# ProtoShieldMega.net
KiCad netlist of a schematic drawn in EAGLE
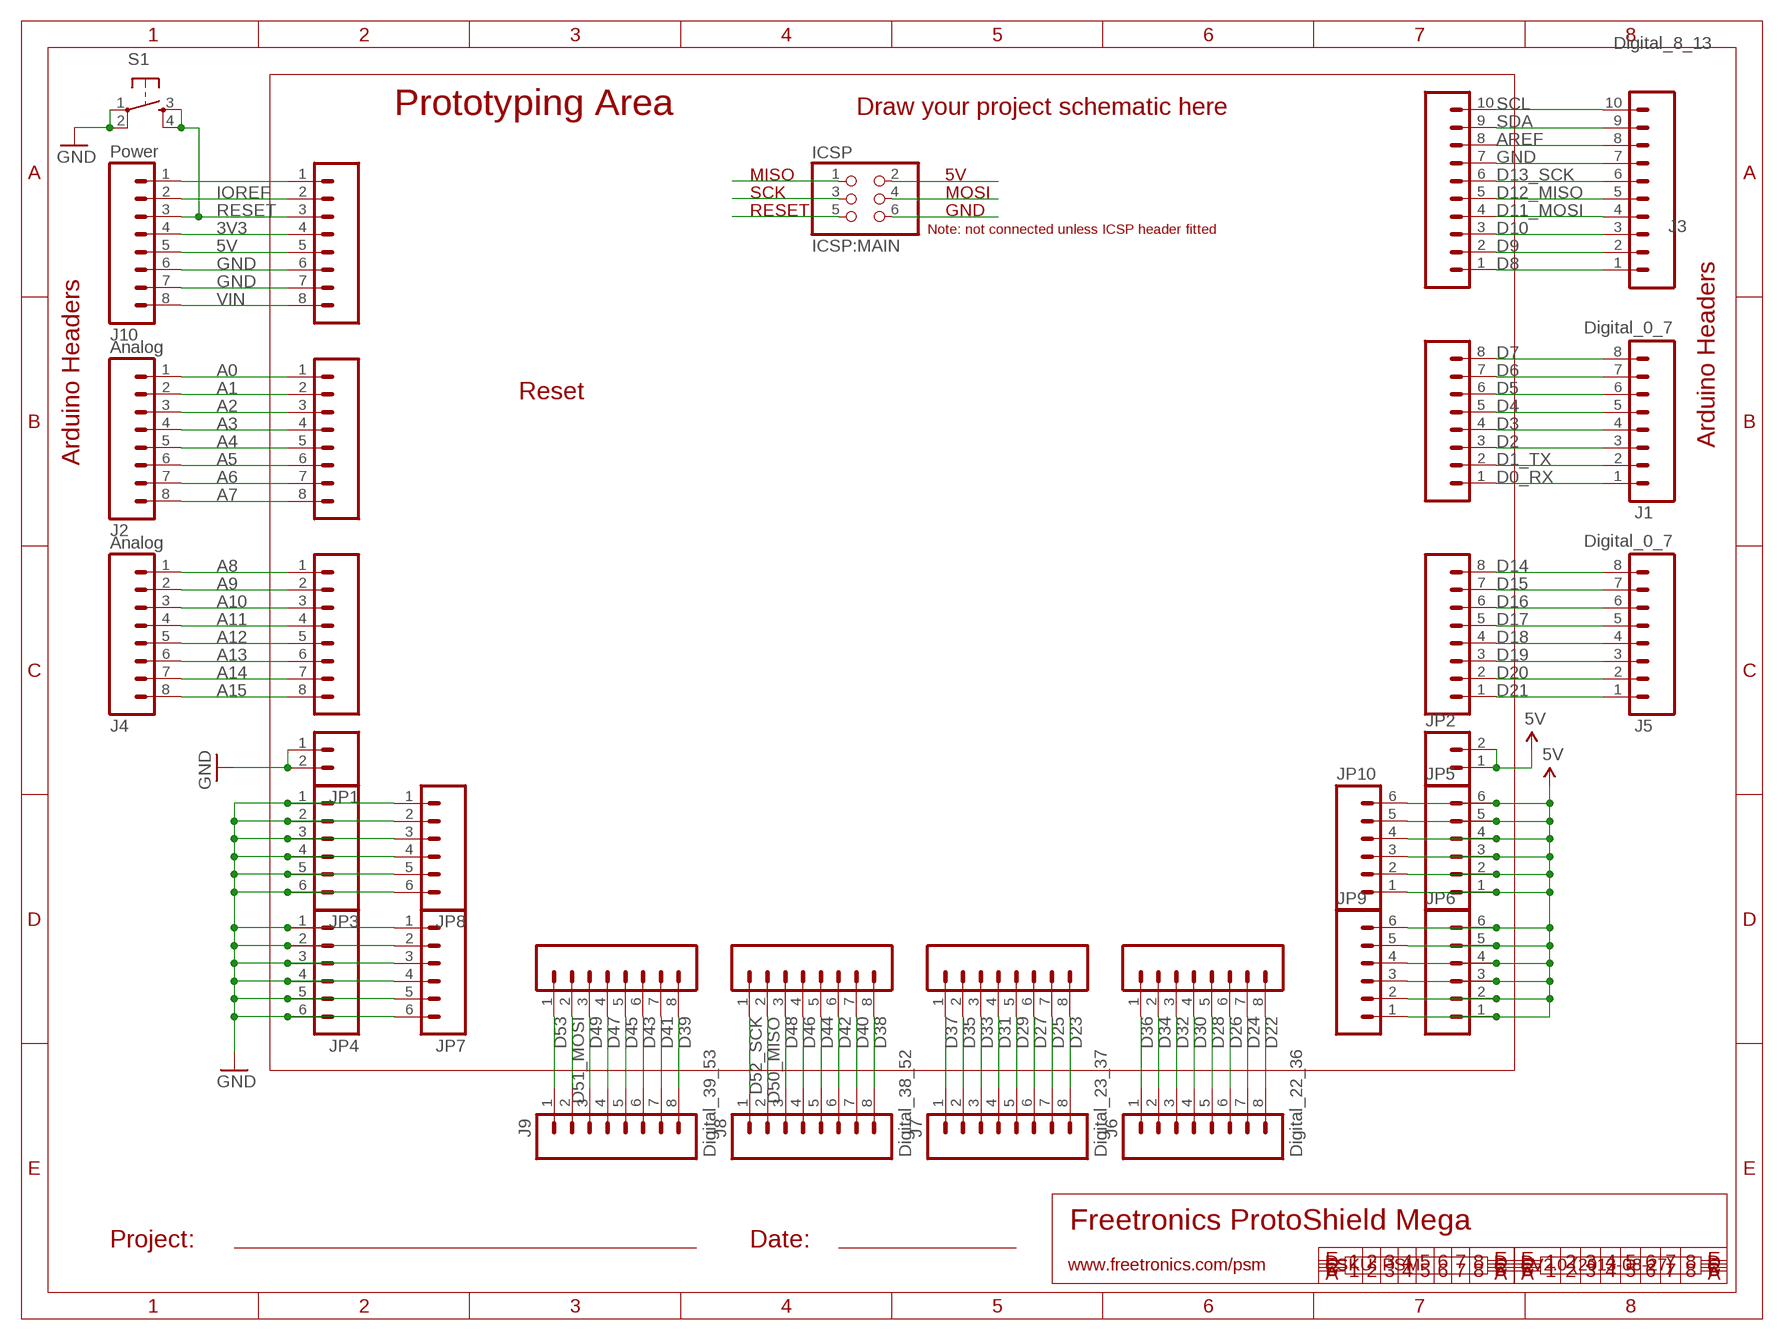
[diagram p0: schematic, sheet 1]

(export (version "E")
  (design (tool "Eeschema 10.0.6"))
  (components
    (comp (ref "ICSP")
      (value "ICSP:MAIN")
      (footprint "eagle-import:2X03")
      (libsource (lib "eagle-import") (part "PINHD-2X3"))
    )
    (comp (ref "J1")
      (value "Digital_0_7")
      (footprint "eagle-import:1X08")
      (libsource (lib "eagle-import") (part "M08"))
    )
    (comp (ref "J2")
      (value "Analog")
      (footprint "eagle-import:1X08")
      (libsource (lib "eagle-import") (part "freetronics-master-v1_M08"))
    )
    (comp (ref "J3")
      (value "Digital_8_13")
      (footprint "eagle-import:1X10")
      (libsource (lib "eagle-import") (part "M100.1"))
    )
    (comp (ref "J4")
      (value "Analog")
      (footprint "eagle-import:1X08")
      (libsource (lib "eagle-import") (part "freetronics-master-v1_M08"))
    )
    (comp (ref "J5")
      (value "Digital_0_7")
      (footprint "eagle-import:1X08")
      (libsource (lib "eagle-import") (part "M08"))
    )
    (comp (ref "J6")
      (value "Digital_22_36")
      (footprint "eagle-import:1X08")
      (libsource (lib "eagle-import") (part "M08"))
    )
    (comp (ref "J7")
      (value "Digital_23_37")
      (footprint "eagle-import:1X08")
      (libsource (lib "eagle-import") (part "M08"))
    )
    (comp (ref "J8")
      (value "Digital_38_52")
      (footprint "eagle-import:1X08")
      (libsource (lib "eagle-import") (part "M08"))
    )
    (comp (ref "J9")
      (value "Digital_39_53")
      (footprint "eagle-import:1X08")
      (libsource (lib "eagle-import") (part "M08"))
    )
    (comp (ref "J10")
      (value "Power")
      (footprint "eagle-import:1X08")
      (libsource (lib "eagle-import") (part "freetronics-master-v1_M08"))
    )
    (comp (ref "JP1")
      (value "M02PTH")
      (footprint "eagle-import:1X02")
      (libsource (lib "eagle-import") (part "M02PTH"))
    )
    (comp (ref "JP2")
      (value "M02PTH")
      (footprint "eagle-import:1X02")
      (libsource (lib "eagle-import") (part "M02PTH"))
    )
    (comp (ref "JP3")
      (value "M06SIP")
      (footprint "eagle-import:1X06")
      (libsource (lib "eagle-import") (part "M06SIP"))
    )
    (comp (ref "JP4")
      (value "M06SIP")
      (footprint "eagle-import:1X06")
      (libsource (lib "eagle-import") (part "M06SIP"))
    )
    (comp (ref "JP5")
      (value "M06SIP")
      (footprint "eagle-import:1X06")
      (libsource (lib "eagle-import") (part "M06SIP"))
    )
    (comp (ref "JP6")
      (value "M06SIP")
      (footprint "eagle-import:1X06")
      (libsource (lib "eagle-import") (part "M06SIP"))
    )
    (comp (ref "JP7")
      (value "M06SIP")
      (footprint "eagle-import:1X06")
      (libsource (lib "eagle-import") (part "M06SIP"))
    )
    (comp (ref "JP8")
      (value "M06SIP")
      (footprint "eagle-import:1X06")
      (libsource (lib "eagle-import") (part "M06SIP"))
    )
    (comp (ref "JP9")
      (value "M06SIP")
      (footprint "eagle-import:1X06")
      (libsource (lib "eagle-import") (part "M06SIP"))
    )
    (comp (ref "JP10")
      (value "M06SIP")
      (footprint "eagle-import:1X06")
      (libsource (lib "eagle-import") (part "M06SIP"))
    )
    (comp (ref "S1")
      (value "TAC_SWITCHPTH")
      (footprint "eagle-import:TACTILE-PTH")
      (libsource (lib "eagle-import") (part "TAC_SWITCHPTH"))
    )
    (comp (ref "SL1")
      (value "Digital_0_7")
      (footprint "eagle-import:1X08")
      (libsource (lib "eagle-import") (part "M08"))
    )
    (comp (ref "SL2")
      (value "Analog")
      (footprint "eagle-import:1X08")
      (libsource (lib "eagle-import") (part "freetronics-master-v1_M08"))
    )
    (comp (ref "SL3")
      (value "Digital_8_13")
      (footprint "eagle-import:1X10")
      (libsource (lib "eagle-import") (part "M100.1"))
    )
    (comp (ref "SL4")
      (value "Analog")
      (footprint "eagle-import:1X08")
      (libsource (lib "eagle-import") (part "freetronics-master-v1_M08"))
    )
    (comp (ref "SL5")
      (value "Digital_0_7")
      (footprint "eagle-import:1X08")
      (libsource (lib "eagle-import") (part "M08"))
    )
    (comp (ref "SL6")
      (value "Digital_0_7")
      (footprint "eagle-import:1X08")
      (libsource (lib "eagle-import") (part "M08"))
    )
    (comp (ref "SL7")
      (value "Digital_0_7")
      (footprint "eagle-import:1X08")
      (libsource (lib "eagle-import") (part "M08"))
    )
    (comp (ref "SL8")
      (value "Digital_0_7")
      (footprint "eagle-import:1X08")
      (libsource (lib "eagle-import") (part "M08"))
    )
    (comp (ref "SL9")
      (value "Digital_0_7")
      (footprint "eagle-import:1X08")
      (libsource (lib "eagle-import") (part "M08"))
    )
    (comp (ref "SLP")
      (value "Power")
      (footprint "eagle-import:1X08")
      (libsource (lib "eagle-import") (part "freetronics-master-v1_M08"))
    )
  )
  (nets
    (net (code "1") (name "/3V3") (class "Default")
      (node (ref "J10") (pin "4") (pinfunction "4_4") (pintype "passive"))
      (node (ref "SLP") (pin "4") (pinfunction "4_4") (pintype "passive"))
    )
    (net (code "2") (name "/A0") (class "Default")
      (node (ref "J2") (pin "1") (pinfunction "1_1") (pintype "passive"))
      (node (ref "SL2") (pin "1") (pinfunction "1_1") (pintype "passive"))
    )
    (net (code "3") (name "/A1") (class "Default")
      (node (ref "J2") (pin "2") (pinfunction "2_2") (pintype "passive"))
      (node (ref "SL2") (pin "2") (pinfunction "2_2") (pintype "passive"))
    )
    (net (code "4") (name "/A2") (class "Default")
      (node (ref "J2") (pin "3") (pinfunction "3_3") (pintype "passive"))
      (node (ref "SL2") (pin "3") (pinfunction "3_3") (pintype "passive"))
    )
    (net (code "5") (name "/A3") (class "Default")
      (node (ref "J2") (pin "4") (pinfunction "4_4") (pintype "passive"))
      (node (ref "SL2") (pin "4") (pinfunction "4_4") (pintype "passive"))
    )
    (net (code "6") (name "/A4") (class "Default")
      (node (ref "J2") (pin "5") (pinfunction "5_5") (pintype "passive"))
      (node (ref "SL2") (pin "5") (pinfunction "5_5") (pintype "passive"))
    )
    (net (code "7") (name "/A5") (class "Default")
      (node (ref "J2") (pin "6") (pinfunction "6_6") (pintype "passive"))
      (node (ref "SL2") (pin "6") (pinfunction "6_6") (pintype "passive"))
    )
    (net (code "8") (name "/A6") (class "Default")
      (node (ref "J2") (pin "7") (pinfunction "7_7") (pintype "passive"))
      (node (ref "SL2") (pin "7") (pinfunction "7_7") (pintype "passive"))
    )
    (net (code "9") (name "/A7") (class "Default")
      (node (ref "J2") (pin "8") (pinfunction "8_8") (pintype "passive"))
      (node (ref "SL2") (pin "8") (pinfunction "8_8") (pintype "passive"))
    )
    (net (code "10") (name "/A8") (class "Default")
      (node (ref "J4") (pin "1") (pinfunction "1_1") (pintype "passive"))
      (node (ref "SL4") (pin "1") (pinfunction "1_1") (pintype "passive"))
    )
    (net (code "11") (name "/A9") (class "Default")
      (node (ref "J4") (pin "2") (pinfunction "2_2") (pintype "passive"))
      (node (ref "SL4") (pin "2") (pinfunction "2_2") (pintype "passive"))
    )
    (net (code "12") (name "/A10") (class "Default")
      (node (ref "J4") (pin "3") (pinfunction "3_3") (pintype "passive"))
      (node (ref "SL4") (pin "3") (pinfunction "3_3") (pintype "passive"))
    )
    (net (code "13") (name "/A11") (class "Default")
      (node (ref "J4") (pin "4") (pinfunction "4_4") (pintype "passive"))
      (node (ref "SL4") (pin "4") (pinfunction "4_4") (pintype "passive"))
    )
    (net (code "14") (name "/A12") (class "Default")
      (node (ref "J4") (pin "5") (pinfunction "5_5") (pintype "passive"))
      (node (ref "SL4") (pin "5") (pinfunction "5_5") (pintype "passive"))
    )
    (net (code "15") (name "/A13") (class "Default")
      (node (ref "J4") (pin "6") (pinfunction "6_6") (pintype "passive"))
      (node (ref "SL4") (pin "6") (pinfunction "6_6") (pintype "passive"))
    )
    (net (code "16") (name "/A14") (class "Default")
      (node (ref "J4") (pin "7") (pinfunction "7_7") (pintype "passive"))
      (node (ref "SL4") (pin "7") (pinfunction "7_7") (pintype "passive"))
    )
    (net (code "17") (name "/A15") (class "Default")
      (node (ref "J4") (pin "8") (pinfunction "8_8") (pintype "passive"))
      (node (ref "SL4") (pin "8") (pinfunction "8_8") (pintype "passive"))
    )
    (net (code "18") (name "/AREF") (class "Default")
      (node (ref "J3") (pin "8") (pinfunction "8_8") (pintype "passive"))
      (node (ref "SL3") (pin "8") (pinfunction "8_8") (pintype "passive"))
    )
    (net (code "19") (name "/D0_RX") (class "Default")
      (node (ref "J1") (pin "1") (pinfunction "1_1") (pintype "passive"))
      (node (ref "SL1") (pin "1") (pinfunction "1_1") (pintype "passive"))
    )
    (net (code "20") (name "/D1_TX") (class "Default")
      (node (ref "J1") (pin "2") (pinfunction "2_2") (pintype "passive"))
      (node (ref "SL1") (pin "2") (pinfunction "2_2") (pintype "passive"))
    )
    (net (code "21") (name "/D2") (class "Default")
      (node (ref "J1") (pin "3") (pinfunction "3_3") (pintype "passive"))
      (node (ref "SL1") (pin "3") (pinfunction "3_3") (pintype "passive"))
    )
    (net (code "22") (name "/D3") (class "Default")
      (node (ref "J1") (pin "4") (pinfunction "4_4") (pintype "passive"))
      (node (ref "SL1") (pin "4") (pinfunction "4_4") (pintype "passive"))
    )
    (net (code "23") (name "/D4") (class "Default")
      (node (ref "J1") (pin "5") (pinfunction "5_5") (pintype "passive"))
      (node (ref "SL1") (pin "5") (pinfunction "5_5") (pintype "passive"))
    )
    (net (code "24") (name "/D5") (class "Default")
      (node (ref "J1") (pin "6") (pinfunction "6_6") (pintype "passive"))
      (node (ref "SL1") (pin "6") (pinfunction "6_6") (pintype "passive"))
    )
    (net (code "25") (name "/D6") (class "Default")
      (node (ref "J1") (pin "7") (pinfunction "7_7") (pintype "passive"))
      (node (ref "SL1") (pin "7") (pinfunction "7_7") (pintype "passive"))
    )
    (net (code "26") (name "/D7") (class "Default")
      (node (ref "J1") (pin "8") (pinfunction "8_8") (pintype "passive"))
      (node (ref "SL1") (pin "8") (pinfunction "8_8") (pintype "passive"))
    )
    (net (code "27") (name "/D8") (class "Default")
      (node (ref "J3") (pin "1") (pinfunction "1_1") (pintype "passive"))
      (node (ref "SL3") (pin "1") (pinfunction "1_1") (pintype "passive"))
    )
    (net (code "28") (name "/D9") (class "Default")
      (node (ref "J3") (pin "2") (pinfunction "2_2") (pintype "passive"))
      (node (ref "SL3") (pin "2") (pinfunction "2_2") (pintype "passive"))
    )
    (net (code "29") (name "/D10") (class "Default")
      (node (ref "J3") (pin "3") (pinfunction "3_3") (pintype "passive"))
      (node (ref "SL3") (pin "3") (pinfunction "3_3") (pintype "passive"))
    )
    (net (code "30") (name "/D11_MOSI") (class "Default")
      (node (ref "J3") (pin "4") (pinfunction "4_4") (pintype "passive"))
      (node (ref "SL3") (pin "4") (pinfunction "4_4") (pintype "passive"))
    )
    (net (code "31") (name "/D12_MISO") (class "Default")
      (node (ref "J3") (pin "5") (pinfunction "5_5") (pintype "passive"))
      (node (ref "SL3") (pin "5") (pinfunction "5_5") (pintype "passive"))
    )
    (net (code "32") (name "/D13_SCK") (class "Default")
      (node (ref "J3") (pin "6") (pinfunction "6_6") (pintype "passive"))
      (node (ref "SL3") (pin "6") (pinfunction "6_6") (pintype "passive"))
    )
    (net (code "33") (name "/D14") (class "Default")
      (node (ref "J5") (pin "8") (pinfunction "8_8") (pintype "passive"))
      (node (ref "SL5") (pin "8") (pinfunction "8_8") (pintype "passive"))
    )
    (net (code "34") (name "/D15") (class "Default")
      (node (ref "J5") (pin "7") (pinfunction "7_7") (pintype "passive"))
      (node (ref "SL5") (pin "7") (pinfunction "7_7") (pintype "passive"))
    )
    (net (code "35") (name "/D16") (class "Default")
      (node (ref "J5") (pin "6") (pinfunction "6_6") (pintype "passive"))
      (node (ref "SL5") (pin "6") (pinfunction "6_6") (pintype "passive"))
    )
    (net (code "36") (name "/D17") (class "Default")
      (node (ref "J5") (pin "5") (pinfunction "5_5") (pintype "passive"))
      (node (ref "SL5") (pin "5") (pinfunction "5_5") (pintype "passive"))
    )
    (net (code "37") (name "/D18") (class "Default")
      (node (ref "J5") (pin "4") (pinfunction "4_4") (pintype "passive"))
      (node (ref "SL5") (pin "4") (pinfunction "4_4") (pintype "passive"))
    )
    (net (code "38") (name "/D19") (class "Default")
      (node (ref "J5") (pin "3") (pinfunction "3_3") (pintype "passive"))
      (node (ref "SL5") (pin "3") (pinfunction "3_3") (pintype "passive"))
    )
    (net (code "39") (name "/D20") (class "Default")
      (node (ref "J5") (pin "2") (pinfunction "2_2") (pintype "passive"))
      (node (ref "SL5") (pin "2") (pinfunction "2_2") (pintype "passive"))
    )
    (net (code "40") (name "/D21") (class "Default")
      (node (ref "J5") (pin "1") (pinfunction "1_1") (pintype "passive"))
      (node (ref "SL5") (pin "1") (pinfunction "1_1") (pintype "passive"))
    )
    (net (code "41") (name "/D22") (class "Default")
      (node (ref "J6") (pin "8") (pinfunction "8_8") (pintype "passive"))
      (node (ref "SL6") (pin "8") (pinfunction "8_8") (pintype "passive"))
    )
    (net (code "42") (name "/D23") (class "Default")
      (node (ref "J7") (pin "8") (pinfunction "8_8") (pintype "passive"))
      (node (ref "SL7") (pin "8") (pinfunction "8_8") (pintype "passive"))
    )
    (net (code "43") (name "/D24") (class "Default")
      (node (ref "J6") (pin "7") (pinfunction "7_7") (pintype "passive"))
      (node (ref "SL6") (pin "7") (pinfunction "7_7") (pintype "passive"))
    )
    (net (code "44") (name "/D25") (class "Default")
      (node (ref "J7") (pin "7") (pinfunction "7_7") (pintype "passive"))
      (node (ref "SL7") (pin "7") (pinfunction "7_7") (pintype "passive"))
    )
    (net (code "45") (name "/D26") (class "Default")
      (node (ref "J6") (pin "6") (pinfunction "6_6") (pintype "passive"))
      (node (ref "SL6") (pin "6") (pinfunction "6_6") (pintype "passive"))
    )
    (net (code "46") (name "/D27") (class "Default")
      (node (ref "J7") (pin "6") (pinfunction "6_6") (pintype "passive"))
      (node (ref "SL7") (pin "6") (pinfunction "6_6") (pintype "passive"))
    )
    (net (code "47") (name "/D28") (class "Default")
      (node (ref "J6") (pin "5") (pinfunction "5_5") (pintype "passive"))
      (node (ref "SL6") (pin "5") (pinfunction "5_5") (pintype "passive"))
    )
    (net (code "48") (name "/D29") (class "Default")
      (node (ref "J7") (pin "5") (pinfunction "5_5") (pintype "passive"))
      (node (ref "SL7") (pin "5") (pinfunction "5_5") (pintype "passive"))
    )
    (net (code "49") (name "/D30") (class "Default")
      (node (ref "J6") (pin "4") (pinfunction "4_4") (pintype "passive"))
      (node (ref "SL6") (pin "4") (pinfunction "4_4") (pintype "passive"))
    )
    (net (code "50") (name "/D31") (class "Default")
      (node (ref "J7") (pin "4") (pinfunction "4_4") (pintype "passive"))
      (node (ref "SL7") (pin "4") (pinfunction "4_4") (pintype "passive"))
    )
    (net (code "51") (name "/D32") (class "Default")
      (node (ref "J6") (pin "3") (pinfunction "3_3") (pintype "passive"))
      (node (ref "SL6") (pin "3") (pinfunction "3_3") (pintype "passive"))
    )
    (net (code "52") (name "/D33") (class "Default")
      (node (ref "J7") (pin "3") (pinfunction "3_3") (pintype "passive"))
      (node (ref "SL7") (pin "3") (pinfunction "3_3") (pintype "passive"))
    )
    (net (code "53") (name "/D34") (class "Default")
      (node (ref "J6") (pin "2") (pinfunction "2_2") (pintype "passive"))
      (node (ref "SL6") (pin "2") (pinfunction "2_2") (pintype "passive"))
    )
    (net (code "54") (name "/D35") (class "Default")
      (node (ref "J7") (pin "2") (pinfunction "2_2") (pintype "passive"))
      (node (ref "SL7") (pin "2") (pinfunction "2_2") (pintype "passive"))
    )
    (net (code "55") (name "/D36") (class "Default")
      (node (ref "J6") (pin "1") (pinfunction "1_1") (pintype "passive"))
      (node (ref "SL6") (pin "1") (pinfunction "1_1") (pintype "passive"))
    )
    (net (code "56") (name "/D37") (class "Default")
      (node (ref "J7") (pin "1") (pinfunction "1_1") (pintype "passive"))
      (node (ref "SL7") (pin "1") (pinfunction "1_1") (pintype "passive"))
    )
    (net (code "57") (name "/D38") (class "Default")
      (node (ref "J8") (pin "8") (pinfunction "8_8") (pintype "passive"))
      (node (ref "SL8") (pin "8") (pinfunction "8_8") (pintype "passive"))
    )
    (net (code "58") (name "/D39") (class "Default")
      (node (ref "J9") (pin "8") (pinfunction "8_8") (pintype "passive"))
      (node (ref "SL9") (pin "8") (pinfunction "8_8") (pintype "passive"))
    )
    (net (code "59") (name "/D40") (class "Default")
      (node (ref "J8") (pin "7") (pinfunction "7_7") (pintype "passive"))
      (node (ref "SL8") (pin "7") (pinfunction "7_7") (pintype "passive"))
    )
    (net (code "60") (name "/D41") (class "Default")
      (node (ref "J9") (pin "7") (pinfunction "7_7") (pintype "passive"))
      (node (ref "SL9") (pin "7") (pinfunction "7_7") (pintype "passive"))
    )
    (net (code "61") (name "/D42") (class "Default")
      (node (ref "J8") (pin "6") (pinfunction "6_6") (pintype "passive"))
      (node (ref "SL8") (pin "6") (pinfunction "6_6") (pintype "passive"))
    )
    (net (code "62") (name "/D43") (class "Default")
      (node (ref "J9") (pin "6") (pinfunction "6_6") (pintype "passive"))
      (node (ref "SL9") (pin "6") (pinfunction "6_6") (pintype "passive"))
    )
    (net (code "63") (name "/D44") (class "Default")
      (node (ref "J8") (pin "5") (pinfunction "5_5") (pintype "passive"))
      (node (ref "SL8") (pin "5") (pinfunction "5_5") (pintype "passive"))
    )
    (net (code "64") (name "/D45") (class "Default")
      (node (ref "J9") (pin "5") (pinfunction "5_5") (pintype "passive"))
      (node (ref "SL9") (pin "5") (pinfunction "5_5") (pintype "passive"))
    )
    (net (code "65") (name "/D46") (class "Default")
      (node (ref "J8") (pin "4") (pinfunction "4_4") (pintype "passive"))
      (node (ref "SL8") (pin "4") (pinfunction "4_4") (pintype "passive"))
    )
    (net (code "66") (name "/D47") (class "Default")
      (node (ref "J9") (pin "4") (pinfunction "4_4") (pintype "passive"))
      (node (ref "SL9") (pin "4") (pinfunction "4_4") (pintype "passive"))
    )
    (net (code "67") (name "/D48") (class "Default")
      (node (ref "J8") (pin "3") (pinfunction "3_3") (pintype "passive"))
      (node (ref "SL8") (pin "3") (pinfunction "3_3") (pintype "passive"))
    )
    (net (code "68") (name "/D49") (class "Default")
      (node (ref "J9") (pin "3") (pinfunction "3_3") (pintype "passive"))
      (node (ref "SL9") (pin "3") (pinfunction "3_3") (pintype "passive"))
    )
    (net (code "69") (name "/D50_MISO") (class "Default")
      (node (ref "J8") (pin "2") (pinfunction "2_2") (pintype "passive"))
      (node (ref "SL8") (pin "2") (pinfunction "2_2") (pintype "passive"))
    )
    (net (code "70") (name "/D51_MOSI") (class "Default")
      (node (ref "J9") (pin "2") (pinfunction "2_2") (pintype "passive"))
      (node (ref "SL9") (pin "2") (pinfunction "2_2") (pintype "passive"))
    )
    (net (code "71") (name "/D52_SCK") (class "Default")
      (node (ref "J8") (pin "1") (pinfunction "1_1") (pintype "passive"))
      (node (ref "SL8") (pin "1") (pinfunction "1_1") (pintype "passive"))
    )
    (net (code "72") (name "/D53") (class "Default")
      (node (ref "J9") (pin "1") (pinfunction "1_1") (pintype "passive"))
      (node (ref "SL9") (pin "1") (pinfunction "1_1") (pintype "passive"))
    )
    (net (code "73") (name "/IOREF") (class "Default")
      (node (ref "J10") (pin "2") (pinfunction "2_2") (pintype "passive"))
      (node (ref "SLP") (pin "2") (pinfunction "2_2") (pintype "passive"))
    )
    (net (code "74") (name "/RESET") (class "Default")
      (node (ref "J10") (pin "3") (pinfunction "3_3") (pintype "passive"))
      (node (ref "S1") (pin "3") (pinfunction "3_3") (pintype "passive"))
      (node (ref "S1") (pin "4") (pinfunction "4_4") (pintype "passive"))
      (node (ref "SLP") (pin "3") (pinfunction "3_3") (pintype "passive"))
    )
    (net (code "75") (name "/SCL") (class "Default")
      (node (ref "J3") (pin "10") (pinfunction "10_10") (pintype "passive"))
      (node (ref "SL3") (pin "10") (pinfunction "10_10") (pintype "passive"))
    )
    (net (code "76") (name "/SDA") (class "Default")
      (node (ref "J3") (pin "9") (pinfunction "9_9") (pintype "passive"))
      (node (ref "SL3") (pin "9") (pinfunction "9_9") (pintype "passive"))
    )
    (net (code "77") (name "/VIN") (class "Default")
      (node (ref "J10") (pin "8") (pinfunction "8_8") (pintype "passive"))
      (node (ref "SLP") (pin "8") (pinfunction "8_8") (pintype "passive"))
    )
    (net (code "78") (name "5V") (class "Default")
      (node (ref "J10") (pin "5") (pinfunction "5_5") (pintype "passive"))
      (node (ref "JP10") (pin "1") (pinfunction "1_1") (pintype "passive"))
      (node (ref "JP10") (pin "2") (pinfunction "2_2") (pintype "passive"))
      (node (ref "JP10") (pin "3") (pinfunction "3_3") (pintype "passive"))
      (node (ref "JP10") (pin "4") (pinfunction "4_4") (pintype "passive"))
      (node (ref "JP10") (pin "5") (pinfunction "5_5") (pintype "passive"))
      (node (ref "JP10") (pin "6") (pinfunction "6_6") (pintype "passive"))
      (node (ref "JP2") (pin "1") (pinfunction "1_1") (pintype "passive"))
      (node (ref "JP2") (pin "2") (pinfunction "2_2") (pintype "passive"))
      (node (ref "JP5") (pin "1") (pinfunction "1_1") (pintype "passive"))
      (node (ref "JP5") (pin "2") (pinfunction "2_2") (pintype "passive"))
      (node (ref "JP5") (pin "3") (pinfunction "3_3") (pintype "passive"))
      (node (ref "JP5") (pin "4") (pinfunction "4_4") (pintype "passive"))
      (node (ref "JP5") (pin "5") (pinfunction "5_5") (pintype "passive"))
      (node (ref "JP5") (pin "6") (pinfunction "6_6") (pintype "passive"))
      (node (ref "JP6") (pin "1") (pinfunction "1_1") (pintype "passive"))
      (node (ref "JP6") (pin "2") (pinfunction "2_2") (pintype "passive"))
      (node (ref "JP6") (pin "3") (pinfunction "3_3") (pintype "passive"))
      (node (ref "JP6") (pin "4") (pinfunction "4_4") (pintype "passive"))
      (node (ref "JP6") (pin "5") (pinfunction "5_5") (pintype "passive"))
      (node (ref "JP6") (pin "6") (pinfunction "6_6") (pintype "passive"))
      (node (ref "JP9") (pin "1") (pinfunction "1_1") (pintype "passive"))
      (node (ref "JP9") (pin "2") (pinfunction "2_2") (pintype "passive"))
      (node (ref "JP9") (pin "3") (pinfunction "3_3") (pintype "passive"))
      (node (ref "JP9") (pin "4") (pinfunction "4_4") (pintype "passive"))
      (node (ref "JP9") (pin "5") (pinfunction "5_5") (pintype "passive"))
      (node (ref "JP9") (pin "6") (pinfunction "6_6") (pintype "passive"))
      (node (ref "SLP") (pin "5") (pinfunction "5_5") (pintype "passive"))
    )
    (net (code "79") (name "GND") (class "Default")
      (node (ref "J10") (pin "6") (pinfunction "6_6") (pintype "passive"))
      (node (ref "J10") (pin "7") (pinfunction "7_7") (pintype "passive"))
      (node (ref "J3") (pin "7") (pinfunction "7_7") (pintype "passive"))
      (node (ref "JP1") (pin "1") (pinfunction "1_1") (pintype "passive"))
      (node (ref "JP1") (pin "2") (pinfunction "2_2") (pintype "passive"))
      (node (ref "JP3") (pin "1") (pinfunction "1_1") (pintype "passive"))
      (node (ref "JP3") (pin "2") (pinfunction "2_2") (pintype "passive"))
      (node (ref "JP3") (pin "3") (pinfunction "3_3") (pintype "passive"))
      (node (ref "JP3") (pin "4") (pinfunction "4_4") (pintype "passive"))
      (node (ref "JP3") (pin "5") (pinfunction "5_5") (pintype "passive"))
      (node (ref "JP3") (pin "6") (pinfunction "6_6") (pintype "passive"))
      (node (ref "JP4") (pin "1") (pinfunction "1_1") (pintype "passive"))
      (node (ref "JP4") (pin "2") (pinfunction "2_2") (pintype "passive"))
      (node (ref "JP4") (pin "3") (pinfunction "3_3") (pintype "passive"))
      (node (ref "JP4") (pin "4") (pinfunction "4_4") (pintype "passive"))
      (node (ref "JP4") (pin "5") (pinfunction "5_5") (pintype "passive"))
      (node (ref "JP4") (pin "6") (pinfunction "6_6") (pintype "passive"))
      (node (ref "JP7") (pin "1") (pinfunction "1_1") (pintype "passive"))
      (node (ref "JP7") (pin "2") (pinfunction "2_2") (pintype "passive"))
      (node (ref "JP7") (pin "3") (pinfunction "3_3") (pintype "passive"))
      (node (ref "JP7") (pin "4") (pinfunction "4_4") (pintype "passive"))
      (node (ref "JP7") (pin "5") (pinfunction "5_5") (pintype "passive"))
      (node (ref "JP7") (pin "6") (pinfunction "6_6") (pintype "passive"))
      (node (ref "JP8") (pin "1") (pinfunction "1_1") (pintype "passive"))
      (node (ref "JP8") (pin "2") (pinfunction "2_2") (pintype "passive"))
      (node (ref "JP8") (pin "3") (pinfunction "3_3") (pintype "passive"))
      (node (ref "JP8") (pin "4") (pinfunction "4_4") (pintype "passive"))
      (node (ref "JP8") (pin "5") (pinfunction "5_5") (pintype "passive"))
      (node (ref "JP8") (pin "6") (pinfunction "6_6") (pintype "passive"))
      (node (ref "S1") (pin "1") (pinfunction "1_1") (pintype "passive"))
      (node (ref "S1") (pin "2") (pinfunction "2_2") (pintype "passive"))
      (node (ref "SL3") (pin "7") (pinfunction "7_7") (pintype "passive"))
      (node (ref "SLP") (pin "6") (pinfunction "6_6") (pintype "passive"))
      (node (ref "SLP") (pin "7") (pinfunction "7_7") (pintype "passive"))
    )
    (net (code "80") (name "Net-(J10-Pad1)") (class "Default")
      (node (ref "J10") (pin "1") (pinfunction "1_1") (pintype "passive"))
      (node (ref "SLP") (pin "1") (pinfunction "1_1") (pintype "passive"))
    )
    (net (code "81") (name "unconnected-(ICSP-Pad1)") (class "Default")
      (node (ref "ICSP") (pin "1") (pinfunction "1_1") (pintype "passive"))
    )
    (net (code "82") (name "unconnected-(ICSP-Pad2)") (class "Default")
      (node (ref "ICSP") (pin "2") (pinfunction "2_2") (pintype "passive"))
    )
    (net (code "83") (name "unconnected-(ICSP-Pad3)") (class "Default")
      (node (ref "ICSP") (pin "3") (pinfunction "3_3") (pintype "passive"))
    )
    (net (code "84") (name "unconnected-(ICSP-Pad4)") (class "Default")
      (node (ref "ICSP") (pin "4") (pinfunction "4_4") (pintype "passive"))
    )
    (net (code "85") (name "unconnected-(ICSP-Pad5)") (class "Default")
      (node (ref "ICSP") (pin "5") (pinfunction "5_5") (pintype "passive"))
    )
    (net (code "86") (name "unconnected-(ICSP-Pad6)") (class "Default")
      (node (ref "ICSP") (pin "6") (pinfunction "6_6") (pintype "passive"))
    )
  )
)
